# FubarStep_v10.net
KiCad netlist of a schematic drawn in EAGLE
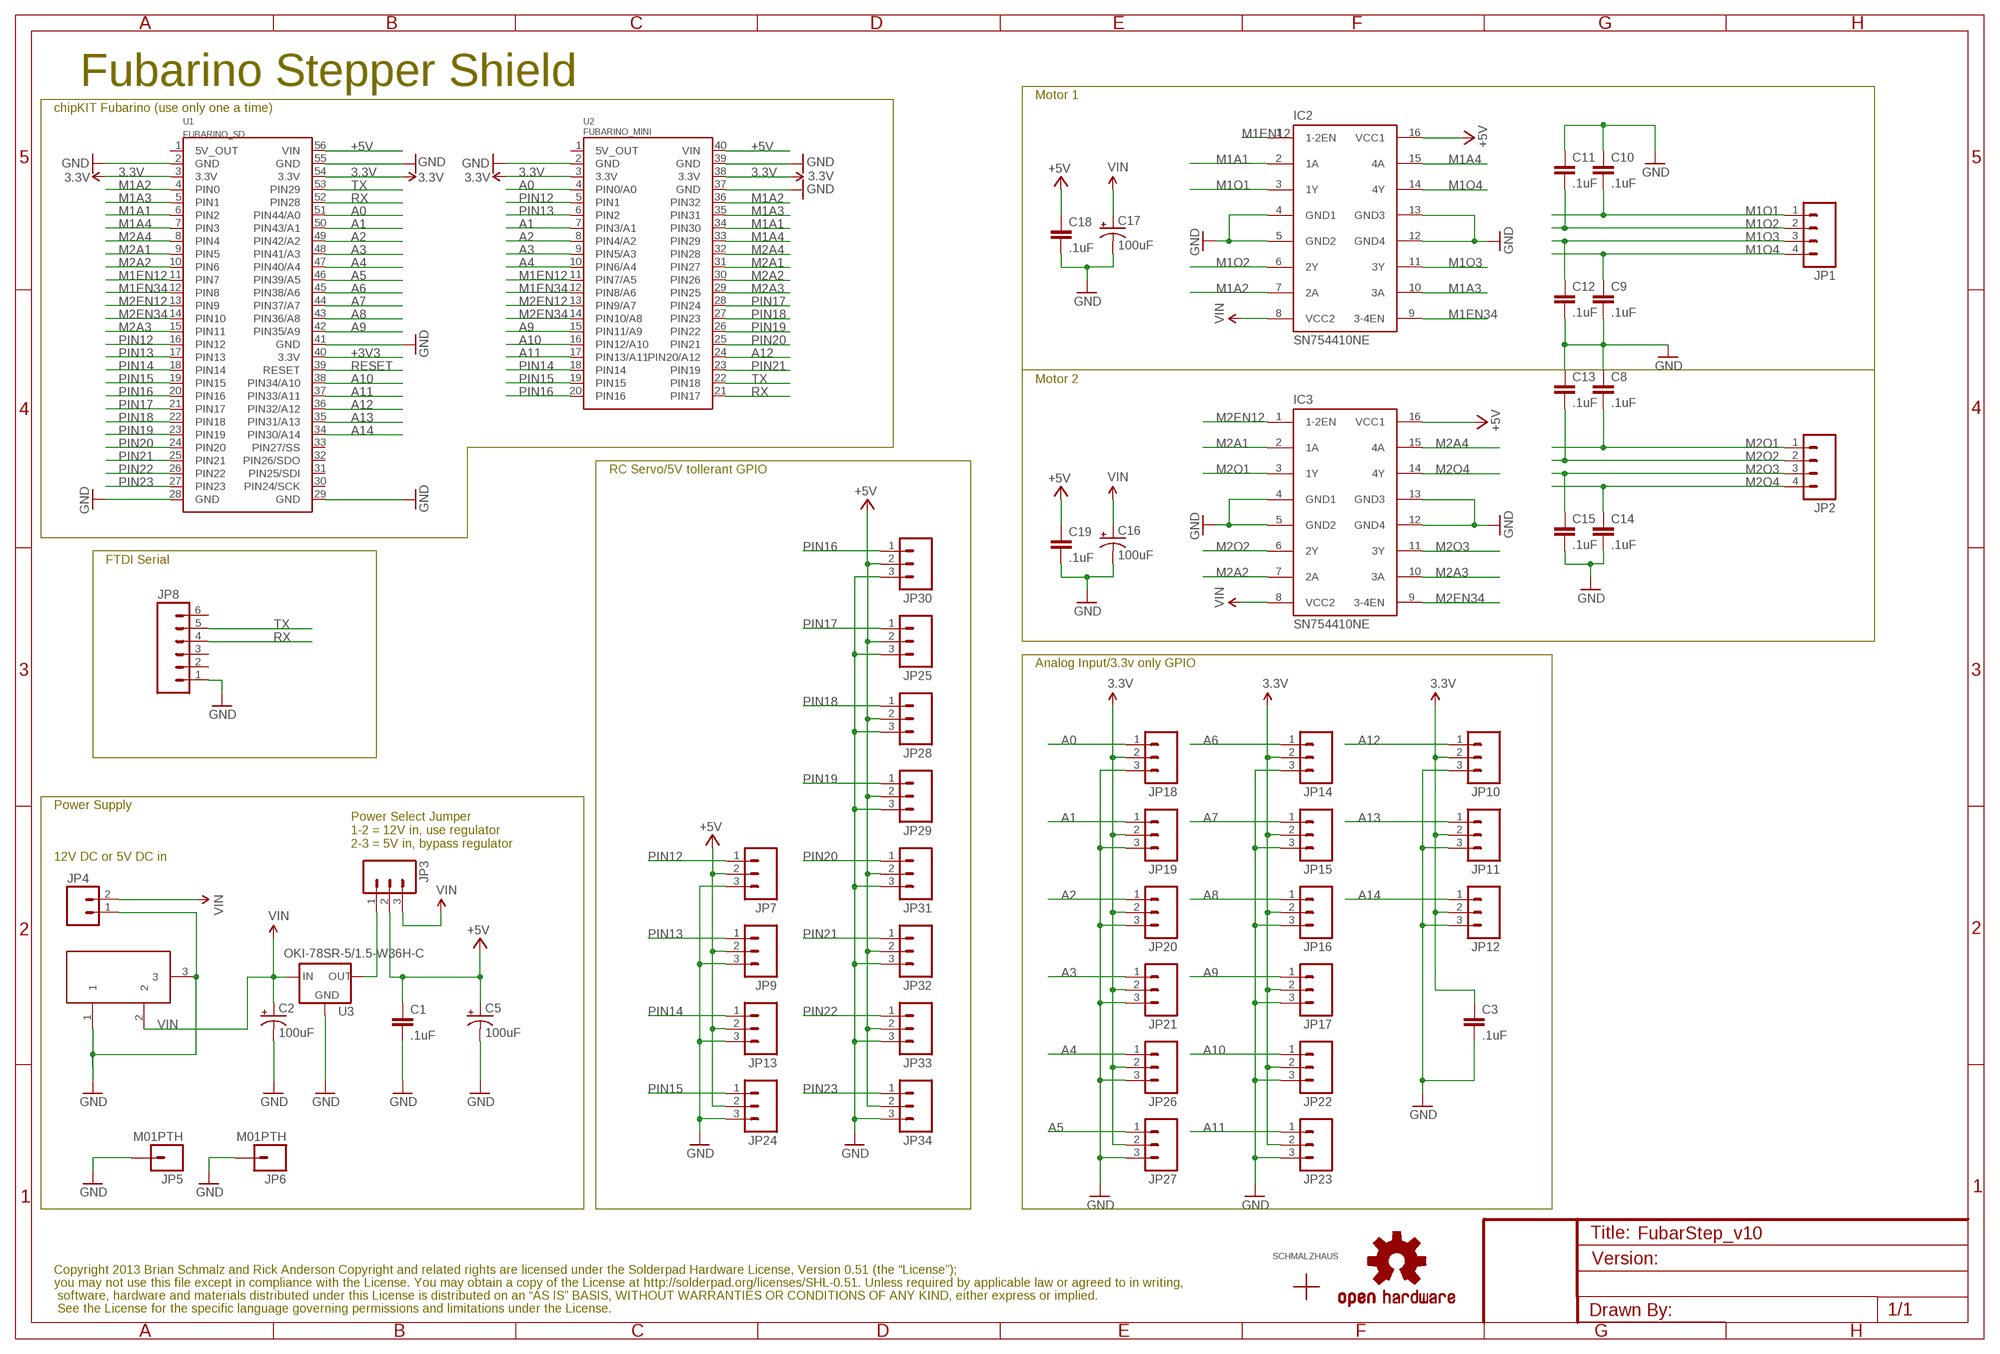
[diagram p0: schematic, sheet 1]

(export (version "E")
  (design (tool "Eeschema 10.0.6"))
  (components
    (comp (ref "C1")
      (value ".1uF")
      (footprint "eagle-import:CAP-PTH-SMALL")
      (libsource (lib "eagle-import") (part "CAPPTH"))
    )
    (comp (ref "C2")
      (value "100uF")
      (footprint "eagle-import:CPOL-RADIAL-100UF-25V")
      (libsource (lib "eagle-import") (part "CAP_POLPTH1"))
    )
    (comp (ref "C3")
      (value ".1uF")
      (footprint "eagle-import:CAP-PTH-SMALL")
      (libsource (lib "eagle-import") (part "CAPPTH"))
    )
    (comp (ref "C5")
      (value "100uF")
      (footprint "eagle-import:CPOL-RADIAL-100UF-25V")
      (libsource (lib "eagle-import") (part "CAP_POLPTH1"))
    )
    (comp (ref "C8")
      (value ".1uF")
      (footprint "eagle-import:CAP-PTH-SMALL")
      (libsource (lib "eagle-import") (part "CAPPTH"))
    )
    (comp (ref "C9")
      (value ".1uF")
      (footprint "eagle-import:CAP-PTH-SMALL")
      (libsource (lib "eagle-import") (part "CAPPTH"))
    )
    (comp (ref "C10")
      (value ".1uF")
      (footprint "eagle-import:CAP-PTH-SMALL")
      (libsource (lib "eagle-import") (part "CAPPTH"))
    )
    (comp (ref "C11")
      (value ".1uF")
      (footprint "eagle-import:CAP-PTH-SMALL")
      (libsource (lib "eagle-import") (part "CAPPTH"))
    )
    (comp (ref "C12")
      (value ".1uF")
      (footprint "eagle-import:CAP-PTH-SMALL")
      (libsource (lib "eagle-import") (part "CAPPTH"))
    )
    (comp (ref "C13")
      (value ".1uF")
      (footprint "eagle-import:CAP-PTH-SMALL")
      (libsource (lib "eagle-import") (part "CAPPTH"))
    )
    (comp (ref "C14")
      (value ".1uF")
      (footprint "eagle-import:CAP-PTH-SMALL")
      (libsource (lib "eagle-import") (part "CAPPTH"))
    )
    (comp (ref "C15")
      (value ".1uF")
      (footprint "eagle-import:CAP-PTH-SMALL")
      (libsource (lib "eagle-import") (part "CAPPTH"))
    )
    (comp (ref "C16")
      (value "100uF")
      (footprint "eagle-import:CPOL-RADIAL-100UF-25V")
      (libsource (lib "eagle-import") (part "CAP_POLPTH1"))
    )
    (comp (ref "C17")
      (value "100uF")
      (footprint "eagle-import:CPOL-RADIAL-100UF-25V")
      (libsource (lib "eagle-import") (part "CAP_POLPTH1"))
    )
    (comp (ref "C18")
      (value ".1uF")
      (footprint "eagle-import:CAP-PTH-SMALL")
      (libsource (lib "eagle-import") (part "CAPPTH"))
    )
    (comp (ref "C19")
      (value ".1uF")
      (footprint "eagle-import:CAP-PTH-SMALL")
      (libsource (lib "eagle-import") (part "CAPPTH"))
    )
    (comp (ref "IC2")
      (value "SN754410NE")
      (footprint "eagle-import:DIL16")
      (fields (field (name "MF") "Arrow Electronics") (field (name "MPN") "L293E"))
      (libsource (lib "eagle-import") (part "L293E"))
    )
    (comp (ref "IC3")
      (value "SN754410NE")
      (footprint "eagle-import:DIL16")
      (fields (field (name "MF") "Arrow Electronics") (field (name "MPN") "L293E"))
      (libsource (lib "eagle-import") (part "L293E"))
    )
    (comp (ref "JP1")
      (value "M04SCREW_LOCK")
      (footprint "eagle-import:SCREWTERMINAL-3.5MM-4_LOCK")
      (libsource (lib "eagle-import") (part "M04SCREW_LOCK"))
    )
    (comp (ref "JP2")
      (value "M04SCREW_LOCK")
      (footprint "eagle-import:SCREWTERMINAL-3.5MM-4_LOCK")
      (libsource (lib "eagle-import") (part "M04SCREW_LOCK"))
    )
    (comp (ref "JP3")
      (value "M03PTH")
      (footprint "eagle-import:1X03")
      (libsource (lib "eagle-import") (part "M03PTH"))
    )
    (comp (ref "JP4")
      (value "M023.5MM")
      (footprint "eagle-import:SCREWTERMINAL-3.5MM-2")
      (libsource (lib "eagle-import") (part "M023.5MM"))
    )
    (comp (ref "JP5")
      (value "M01PTH")
      (footprint "eagle-import:1X01")
      (libsource (lib "eagle-import") (part "M01PTH"))
    )
    (comp (ref "JP6")
      (value "M01PTH")
      (footprint "eagle-import:1X01")
      (libsource (lib "eagle-import") (part "M01PTH"))
    )
    (comp (ref "JP7")
      (value "M03PTH")
      (footprint "eagle-import:1X03")
      (libsource (lib "eagle-import") (part "M03PTH"))
    )
    (comp (ref "JP8")
      (value "M06LOCK")
      (footprint "eagle-import:1X06_LOCK")
      (libsource (lib "eagle-import") (part "M06LOCK"))
    )
    (comp (ref "JP9")
      (value "M03PTH")
      (footprint "eagle-import:1X03")
      (libsource (lib "eagle-import") (part "M03PTH"))
    )
    (comp (ref "JP10")
      (value "M03PTH")
      (footprint "eagle-import:1X03")
      (libsource (lib "eagle-import") (part "M03PTH"))
    )
    (comp (ref "JP11")
      (value "M03PTH")
      (footprint "eagle-import:1X03")
      (libsource (lib "eagle-import") (part "M03PTH"))
    )
    (comp (ref "JP12")
      (value "M03PTH")
      (footprint "eagle-import:1X03")
      (libsource (lib "eagle-import") (part "M03PTH"))
    )
    (comp (ref "JP13")
      (value "M03PTH")
      (footprint "eagle-import:1X03")
      (libsource (lib "eagle-import") (part "M03PTH"))
    )
    (comp (ref "JP14")
      (value "M03PTH")
      (footprint "eagle-import:1X03")
      (libsource (lib "eagle-import") (part "M03PTH"))
    )
    (comp (ref "JP15")
      (value "M03PTH")
      (footprint "eagle-import:1X03")
      (libsource (lib "eagle-import") (part "M03PTH"))
    )
    (comp (ref "JP16")
      (value "M03PTH")
      (footprint "eagle-import:1X03")
      (libsource (lib "eagle-import") (part "M03PTH"))
    )
    (comp (ref "JP17")
      (value "M03PTH")
      (footprint "eagle-import:1X03")
      (libsource (lib "eagle-import") (part "M03PTH"))
    )
    (comp (ref "JP18")
      (value "M03PTH")
      (footprint "eagle-import:1X03")
      (libsource (lib "eagle-import") (part "M03PTH"))
    )
    (comp (ref "JP19")
      (value "M03PTH")
      (footprint "eagle-import:1X03")
      (libsource (lib "eagle-import") (part "M03PTH"))
    )
    (comp (ref "JP20")
      (value "M03PTH")
      (footprint "eagle-import:1X03")
      (libsource (lib "eagle-import") (part "M03PTH"))
    )
    (comp (ref "JP21")
      (value "M03PTH")
      (footprint "eagle-import:1X03")
      (libsource (lib "eagle-import") (part "M03PTH"))
    )
    (comp (ref "JP22")
      (value "M03PTH")
      (footprint "eagle-import:1X03")
      (libsource (lib "eagle-import") (part "M03PTH"))
    )
    (comp (ref "JP23")
      (value "M03PTH")
      (footprint "eagle-import:1X03")
      (libsource (lib "eagle-import") (part "M03PTH"))
    )
    (comp (ref "JP24")
      (value "M03PTH")
      (footprint "eagle-import:1X03")
      (libsource (lib "eagle-import") (part "M03PTH"))
    )
    (comp (ref "JP25")
      (value "M03PTH")
      (footprint "eagle-import:1X03")
      (libsource (lib "eagle-import") (part "M03PTH"))
    )
    (comp (ref "JP26")
      (value "M03PTH")
      (footprint "eagle-import:1X03")
      (libsource (lib "eagle-import") (part "M03PTH"))
    )
    (comp (ref "JP27")
      (value "M03PTH")
      (footprint "eagle-import:1X03")
      (libsource (lib "eagle-import") (part "M03PTH"))
    )
    (comp (ref "JP28")
      (value "M03PTH")
      (footprint "eagle-import:1X03")
      (libsource (lib "eagle-import") (part "M03PTH"))
    )
    (comp (ref "JP29")
      (value "M03PTH")
      (footprint "eagle-import:1X03")
      (libsource (lib "eagle-import") (part "M03PTH"))
    )
    (comp (ref "JP30")
      (value "M03PTH")
      (footprint "eagle-import:1X03")
      (libsource (lib "eagle-import") (part "M03PTH"))
    )
    (comp (ref "JP31")
      (value "M03PTH")
      (footprint "eagle-import:1X03")
      (libsource (lib "eagle-import") (part "M03PTH"))
    )
    (comp (ref "JP32")
      (value "M03PTH")
      (footprint "eagle-import:1X03")
      (libsource (lib "eagle-import") (part "M03PTH"))
    )
    (comp (ref "JP33")
      (value "M03PTH")
      (footprint "eagle-import:1X03")
      (libsource (lib "eagle-import") (part "M03PTH"))
    )
    (comp (ref "JP34")
      (value "M03PTH")
      (footprint "eagle-import:1X03")
      (libsource (lib "eagle-import") (part "M03PTH"))
    )
    (comp (ref "LOGO1")
      (value "OSHW-LOGOM")
      (footprint "eagle-import:OSHW-LOGO-M")
      (libsource (lib "eagle-import") (part "OSHW-LOGOM"))
    )
    (comp (ref "U$1")
      (value "SCHMALZHAUSSCHMALZHAUS_SMALL")
      (footprint "eagle-import:SCHMALZHAUS_SMALL")
      (libsource (lib "eagle-import") (part "SCHMALZHAUSSCHMALZHAUS_SMALL"))
    )
    (comp (ref "U1")
      (value "FUBARINO_SD")
      (footprint "eagle-import:FUBARINO_SD")
      (libsource (lib "eagle-import") (part "FUBARINO_SD"))
    )
    (comp (ref "U2")
      (value "FUBARINO_MINI")
      (footprint "eagle-import:FUBARINO_MINI")
      (libsource (lib "eagle-import") (part "FUBARINO_MINI"))
    )
    (comp (ref "U3")
      (value "OKI-78SR-5/1.5-W36H-C")
      (footprint "eagle-import:TO220-IGO")
      (libsource (lib "eagle-import") (part "V_REG_78XXSINK"))
    )
    (comp (ref "X1")
      (value "DC21MMX")
      (footprint "eagle-import:DC-21MM")
      (libsource (lib "eagle-import") (part "DC21MMX"))
    )
  )
  (nets
    (net (code "1") (name "+5V") (class "Default")
      (node (ref "C1") (pin "1") (pinfunction "1_1") (pintype "passive"))
      (node (ref "C18") (pin "1") (pinfunction "1_1") (pintype "passive"))
      (node (ref "C19") (pin "1") (pinfunction "1_1") (pintype "passive"))
      (node (ref "C5") (pin "1") (pinfunction "+_1") (pintype "passive"))
      (node (ref "IC2") (pin "16") (pinfunction "VCC1_16") (pintype "power_in"))
      (node (ref "IC3") (pin "16") (pinfunction "VCC1_16") (pintype "power_in"))
      (node (ref "JP13") (pin "2") (pinfunction "2_2") (pintype "passive"))
      (node (ref "JP24") (pin "2") (pinfunction "2_2") (pintype "passive"))
      (node (ref "JP25") (pin "2") (pinfunction "2_2") (pintype "passive"))
      (node (ref "JP28") (pin "2") (pinfunction "2_2") (pintype "passive"))
      (node (ref "JP29") (pin "2") (pinfunction "2_2") (pintype "passive"))
      (node (ref "JP3") (pin "2") (pinfunction "2_2") (pintype "passive"))
      (node (ref "JP30") (pin "2") (pinfunction "2_2") (pintype "passive"))
      (node (ref "JP31") (pin "2") (pinfunction "2_2") (pintype "passive"))
      (node (ref "JP32") (pin "2") (pinfunction "2_2") (pintype "passive"))
      (node (ref "JP33") (pin "2") (pinfunction "2_2") (pintype "passive"))
      (node (ref "JP34") (pin "2") (pinfunction "2_2") (pintype "passive"))
      (node (ref "JP7") (pin "2") (pinfunction "2_2") (pintype "passive"))
      (node (ref "JP9") (pin "2") (pinfunction "2_2") (pintype "passive"))
      (node (ref "U1") (pin "56") (pinfunction "VIN_56") (pintype "bidirectional"))
      (node (ref "U2") (pin "40") (pinfunction "VIN_40") (pintype "bidirectional"))
    )
    (net (code "2") (name "/+3V3") (class "Default")
      (node (ref "U1") (pin "40") (pinfunction "3.3V_40") (pintype "bidirectional"))
    )
    (net (code "3") (name "/A0") (class "Default")
      (node (ref "JP18") (pin "1") (pinfunction "1_1") (pintype "passive"))
      (node (ref "U1") (pin "51") (pinfunction "PIN44/A0_51") (pintype "bidirectional"))
      (node (ref "U2") (pin "4") (pinfunction "PIN0/A0_4") (pintype "bidirectional"))
    )
    (net (code "4") (name "/A1") (class "Default")
      (node (ref "JP19") (pin "1") (pinfunction "1_1") (pintype "passive"))
      (node (ref "U1") (pin "50") (pinfunction "PIN43/A1_50") (pintype "bidirectional"))
      (node (ref "U2") (pin "7") (pinfunction "PIN3/A1_7") (pintype "bidirectional"))
    )
    (net (code "5") (name "/A2") (class "Default")
      (node (ref "JP20") (pin "1") (pinfunction "1_1") (pintype "passive"))
      (node (ref "U1") (pin "49") (pinfunction "PIN42/A2_49") (pintype "bidirectional"))
      (node (ref "U2") (pin "8") (pinfunction "PIN4/A2_8") (pintype "bidirectional"))
    )
    (net (code "6") (name "/A3") (class "Default")
      (node (ref "JP21") (pin "1") (pinfunction "1_1") (pintype "passive"))
      (node (ref "U1") (pin "48") (pinfunction "PIN41/A3_48") (pintype "bidirectional"))
      (node (ref "U2") (pin "9") (pinfunction "PIN5/A3_9") (pintype "bidirectional"))
    )
    (net (code "7") (name "/A4") (class "Default")
      (node (ref "JP26") (pin "1") (pinfunction "1_1") (pintype "passive"))
      (node (ref "U1") (pin "47") (pinfunction "PIN40/A4_47") (pintype "bidirectional"))
      (node (ref "U2") (pin "10") (pinfunction "PIN6/A4_10") (pintype "bidirectional"))
    )
    (net (code "8") (name "/A5") (class "Default")
      (node (ref "JP27") (pin "1") (pinfunction "1_1") (pintype "passive"))
      (node (ref "U1") (pin "46") (pinfunction "PIN39/A5_46") (pintype "bidirectional"))
    )
    (net (code "9") (name "/A6") (class "Default")
      (node (ref "JP14") (pin "1") (pinfunction "1_1") (pintype "passive"))
      (node (ref "U1") (pin "45") (pinfunction "PIN38/A6_45") (pintype "bidirectional"))
    )
    (net (code "10") (name "/A7") (class "Default")
      (node (ref "JP15") (pin "1") (pinfunction "1_1") (pintype "passive"))
      (node (ref "U1") (pin "44") (pinfunction "PIN37/A7_44") (pintype "bidirectional"))
    )
    (net (code "11") (name "/A8") (class "Default")
      (node (ref "JP16") (pin "1") (pinfunction "1_1") (pintype "passive"))
      (node (ref "U1") (pin "43") (pinfunction "PIN36/A8_43") (pintype "bidirectional"))
    )
    (net (code "12") (name "/A9") (class "Default")
      (node (ref "JP17") (pin "1") (pinfunction "1_1") (pintype "passive"))
      (node (ref "U1") (pin "42") (pinfunction "PIN35/A9_42") (pintype "bidirectional"))
      (node (ref "U2") (pin "15") (pinfunction "PIN11/A9_15") (pintype "bidirectional"))
    )
    (net (code "13") (name "/A10") (class "Default")
      (node (ref "JP22") (pin "1") (pinfunction "1_1") (pintype "passive"))
      (node (ref "U1") (pin "38") (pinfunction "PIN34/A10_38") (pintype "bidirectional"))
      (node (ref "U2") (pin "16") (pinfunction "PIN12/A10_16") (pintype "bidirectional"))
    )
    (net (code "14") (name "/A11") (class "Default")
      (node (ref "JP23") (pin "1") (pinfunction "1_1") (pintype "passive"))
      (node (ref "U1") (pin "37") (pinfunction "PIN33/A11_37") (pintype "bidirectional"))
      (node (ref "U2") (pin "17") (pinfunction "PIN13/A11_17") (pintype "bidirectional"))
    )
    (net (code "15") (name "/A12") (class "Default")
      (node (ref "JP10") (pin "1") (pinfunction "1_1") (pintype "passive"))
      (node (ref "U1") (pin "36") (pinfunction "PIN32/A12_36") (pintype "bidirectional"))
      (node (ref "U2") (pin "24") (pinfunction "PIN20/A12_24") (pintype "bidirectional"))
    )
    (net (code "16") (name "/A13") (class "Default")
      (node (ref "JP11") (pin "1") (pinfunction "1_1") (pintype "passive"))
      (node (ref "U1") (pin "35") (pinfunction "PIN31/A13_35") (pintype "bidirectional"))
    )
    (net (code "17") (name "/A14") (class "Default")
      (node (ref "JP12") (pin "1") (pinfunction "1_1") (pintype "passive"))
      (node (ref "U1") (pin "34") (pinfunction "PIN30/A14_34") (pintype "bidirectional"))
    )
    (net (code "18") (name "/M1A1") (class "Default")
      (node (ref "IC2") (pin "2") (pinfunction "1A_2") (pintype "input"))
      (node (ref "U1") (pin "6") (pinfunction "PIN2_6") (pintype "bidirectional"))
      (node (ref "U2") (pin "34") (pinfunction "PIN30_34") (pintype "bidirectional"))
    )
    (net (code "19") (name "/M1A2") (class "Default")
      (node (ref "IC2") (pin "7") (pinfunction "2A_7") (pintype "input"))
      (node (ref "U1") (pin "4") (pinfunction "PIN0_4") (pintype "bidirectional"))
      (node (ref "U2") (pin "36") (pinfunction "PIN32_36") (pintype "bidirectional"))
    )
    (net (code "20") (name "/M1A3") (class "Default")
      (node (ref "IC2") (pin "10") (pinfunction "3A_10") (pintype "input"))
      (node (ref "U1") (pin "5") (pinfunction "PIN1_5") (pintype "bidirectional"))
      (node (ref "U2") (pin "35") (pinfunction "PIN31_35") (pintype "bidirectional"))
    )
    (net (code "21") (name "/M1A4") (class "Default")
      (node (ref "IC2") (pin "15") (pinfunction "4A_15") (pintype "input"))
      (node (ref "U1") (pin "7") (pinfunction "PIN3_7") (pintype "bidirectional"))
      (node (ref "U2") (pin "33") (pinfunction "PIN29_33") (pintype "bidirectional"))
    )
    (net (code "22") (name "/M1EN12") (class "Default")
      (node (ref "IC2") (pin "1") (pinfunction "1-2EN_1") (pintype "input"))
      (node (ref "U1") (pin "11") (pinfunction "PIN7_11") (pintype "bidirectional"))
      (node (ref "U2") (pin "11") (pinfunction "PIN7/A5_11") (pintype "bidirectional"))
    )
    (net (code "23") (name "/M1EN34") (class "Default")
      (node (ref "IC2") (pin "9") (pinfunction "3-4EN_9") (pintype "input"))
      (node (ref "U1") (pin "12") (pinfunction "PIN8_12") (pintype "bidirectional"))
      (node (ref "U2") (pin "12") (pinfunction "PIN8/A6_12") (pintype "bidirectional"))
    )
    (net (code "24") (name "/M1O1") (class "Default")
      (node (ref "C10") (pin "2") (pinfunction "2_2") (pintype "passive"))
      (node (ref "IC2") (pin "3") (pinfunction "1Y_3") (pintype "output"))
      (node (ref "JP1") (pin "1") (pinfunction "1_1") (pintype "passive"))
    )
    (net (code "25") (name "/M1O2") (class "Default")
      (node (ref "C11") (pin "2") (pinfunction "2_2") (pintype "passive"))
      (node (ref "IC2") (pin "6") (pinfunction "2Y_6") (pintype "output"))
      (node (ref "JP1") (pin "2") (pinfunction "2_2") (pintype "passive"))
    )
    (net (code "26") (name "/M1O3") (class "Default")
      (node (ref "C12") (pin "1") (pinfunction "1_1") (pintype "passive"))
      (node (ref "IC2") (pin "11") (pinfunction "3Y_11") (pintype "output"))
      (node (ref "JP1") (pin "3") (pinfunction "3_3") (pintype "passive"))
    )
    (net (code "27") (name "/M1O4") (class "Default")
      (node (ref "C9") (pin "1") (pinfunction "1_1") (pintype "passive"))
      (node (ref "IC2") (pin "14") (pinfunction "4Y_14") (pintype "output"))
      (node (ref "JP1") (pin "4") (pinfunction "4_4") (pintype "passive"))
    )
    (net (code "28") (name "/M2A1") (class "Default")
      (node (ref "IC3") (pin "2") (pinfunction "1A_2") (pintype "input"))
      (node (ref "U1") (pin "9") (pinfunction "PIN5_9") (pintype "bidirectional"))
      (node (ref "U2") (pin "31") (pinfunction "PIN27_31") (pintype "bidirectional"))
    )
    (net (code "29") (name "/M2A2") (class "Default")
      (node (ref "IC3") (pin "7") (pinfunction "2A_7") (pintype "input"))
      (node (ref "U1") (pin "10") (pinfunction "PIN6_10") (pintype "bidirectional"))
      (node (ref "U2") (pin "30") (pinfunction "PIN26_30") (pintype "bidirectional"))
    )
    (net (code "30") (name "/M2A3") (class "Default")
      (node (ref "IC3") (pin "10") (pinfunction "3A_10") (pintype "input"))
      (node (ref "U1") (pin "15") (pinfunction "PIN11_15") (pintype "bidirectional"))
      (node (ref "U2") (pin "29") (pinfunction "PIN25_29") (pintype "bidirectional"))
    )
    (net (code "31") (name "/M2A4") (class "Default")
      (node (ref "IC3") (pin "15") (pinfunction "4A_15") (pintype "input"))
      (node (ref "U1") (pin "8") (pinfunction "PIN4_8") (pintype "bidirectional"))
      (node (ref "U2") (pin "32") (pinfunction "PIN28_32") (pintype "bidirectional"))
    )
    (net (code "32") (name "/M2EN12") (class "Default")
      (node (ref "IC3") (pin "1") (pinfunction "1-2EN_1") (pintype "input"))
      (node (ref "U1") (pin "13") (pinfunction "PIN9_13") (pintype "bidirectional"))
      (node (ref "U2") (pin "13") (pinfunction "PIN9/A7_13") (pintype "bidirectional"))
    )
    (net (code "33") (name "/M2EN34") (class "Default")
      (node (ref "IC3") (pin "9") (pinfunction "3-4EN_9") (pintype "input"))
      (node (ref "U1") (pin "14") (pinfunction "PIN10_14") (pintype "bidirectional"))
      (node (ref "U2") (pin "14") (pinfunction "PIN10/A8_14") (pintype "bidirectional"))
    )
    (net (code "34") (name "/M2O1") (class "Default")
      (node (ref "C8") (pin "2") (pinfunction "2_2") (pintype "passive"))
      (node (ref "IC3") (pin "3") (pinfunction "1Y_3") (pintype "output"))
      (node (ref "JP2") (pin "1") (pinfunction "1_1") (pintype "passive"))
    )
    (net (code "35") (name "/M2O2") (class "Default")
      (node (ref "C13") (pin "2") (pinfunction "2_2") (pintype "passive"))
      (node (ref "IC3") (pin "6") (pinfunction "2Y_6") (pintype "output"))
      (node (ref "JP2") (pin "2") (pinfunction "2_2") (pintype "passive"))
    )
    (net (code "36") (name "/M2O3") (class "Default")
      (node (ref "C15") (pin "1") (pinfunction "1_1") (pintype "passive"))
      (node (ref "IC3") (pin "11") (pinfunction "3Y_11") (pintype "output"))
      (node (ref "JP2") (pin "3") (pinfunction "3_3") (pintype "passive"))
    )
    (net (code "37") (name "/M2O4") (class "Default")
      (node (ref "C14") (pin "1") (pinfunction "1_1") (pintype "passive"))
      (node (ref "IC3") (pin "14") (pinfunction "4Y_14") (pintype "output"))
      (node (ref "JP2") (pin "4") (pinfunction "4_4") (pintype "passive"))
    )
    (net (code "38") (name "/PIN12") (class "Default")
      (node (ref "JP7") (pin "1") (pinfunction "1_1") (pintype "passive"))
      (node (ref "U1") (pin "16") (pinfunction "PIN12_16") (pintype "bidirectional"))
      (node (ref "U2") (pin "5") (pinfunction "PIN1_5") (pintype "bidirectional"))
    )
    (net (code "39") (name "/PIN13") (class "Default")
      (node (ref "JP9") (pin "1") (pinfunction "1_1") (pintype "passive"))
      (node (ref "U1") (pin "17") (pinfunction "PIN13_17") (pintype "bidirectional"))
      (node (ref "U2") (pin "6") (pinfunction "PIN2_6") (pintype "bidirectional"))
    )
    (net (code "40") (name "/PIN14") (class "Default")
      (node (ref "JP13") (pin "1") (pinfunction "1_1") (pintype "passive"))
      (node (ref "U1") (pin "18") (pinfunction "PIN14_18") (pintype "bidirectional"))
      (node (ref "U2") (pin "18") (pinfunction "PIN14_18") (pintype "bidirectional"))
    )
    (net (code "41") (name "/PIN15") (class "Default")
      (node (ref "JP24") (pin "1") (pinfunction "1_1") (pintype "passive"))
      (node (ref "U1") (pin "19") (pinfunction "PIN15_19") (pintype "bidirectional"))
      (node (ref "U2") (pin "19") (pinfunction "PIN15_19") (pintype "bidirectional"))
    )
    (net (code "42") (name "/PIN16") (class "Default")
      (node (ref "JP30") (pin "1") (pinfunction "1_1") (pintype "passive"))
      (node (ref "U1") (pin "20") (pinfunction "PIN16_20") (pintype "bidirectional"))
      (node (ref "U2") (pin "20") (pinfunction "PIN16_20") (pintype "bidirectional"))
    )
    (net (code "43") (name "/PIN17") (class "Default")
      (node (ref "JP25") (pin "1") (pinfunction "1_1") (pintype "passive"))
      (node (ref "U1") (pin "21") (pinfunction "PIN17_21") (pintype "bidirectional"))
      (node (ref "U2") (pin "28") (pinfunction "PIN24_28") (pintype "bidirectional"))
    )
    (net (code "44") (name "/PIN18") (class "Default")
      (node (ref "JP28") (pin "1") (pinfunction "1_1") (pintype "passive"))
      (node (ref "U1") (pin "22") (pinfunction "PIN18_22") (pintype "bidirectional"))
      (node (ref "U2") (pin "27") (pinfunction "PIN23_27") (pintype "bidirectional"))
    )
    (net (code "45") (name "/PIN19") (class "Default")
      (node (ref "JP29") (pin "1") (pinfunction "1_1") (pintype "passive"))
      (node (ref "U1") (pin "23") (pinfunction "PIN19_23") (pintype "bidirectional"))
      (node (ref "U2") (pin "26") (pinfunction "PIN22_26") (pintype "bidirectional"))
    )
    (net (code "46") (name "/PIN20") (class "Default")
      (node (ref "JP31") (pin "1") (pinfunction "1_1") (pintype "passive"))
      (node (ref "U1") (pin "24") (pinfunction "PIN20_24") (pintype "bidirectional"))
      (node (ref "U2") (pin "25") (pinfunction "PIN21_25") (pintype "bidirectional"))
    )
    (net (code "47") (name "/PIN21") (class "Default")
      (node (ref "JP32") (pin "1") (pinfunction "1_1") (pintype "passive"))
      (node (ref "U1") (pin "25") (pinfunction "PIN21_25") (pintype "bidirectional"))
      (node (ref "U2") (pin "23") (pinfunction "PIN19_23") (pintype "bidirectional"))
    )
    (net (code "48") (name "/PIN22") (class "Default")
      (node (ref "JP33") (pin "1") (pinfunction "1_1") (pintype "passive"))
      (node (ref "U1") (pin "26") (pinfunction "PIN22_26") (pintype "bidirectional"))
    )
    (net (code "49") (name "/PIN23") (class "Default")
      (node (ref "JP34") (pin "1") (pinfunction "1_1") (pintype "passive"))
      (node (ref "U1") (pin "27") (pinfunction "PIN23_27") (pintype "bidirectional"))
    )
    (net (code "50") (name "/RESET") (class "Default")
      (node (ref "U1") (pin "39") (pinfunction "RESET_39") (pintype "bidirectional"))
    )
    (net (code "51") (name "/RX") (class "Default")
      (node (ref "JP8") (pin "4") (pinfunction "4_4") (pintype "passive"))
      (node (ref "U1") (pin "52") (pinfunction "PIN28_52") (pintype "bidirectional"))
      (node (ref "U2") (pin "21") (pinfunction "PIN17_21") (pintype "bidirectional"))
    )
    (net (code "52") (name "/TX") (class "Default")
      (node (ref "JP8") (pin "5") (pinfunction "5_5") (pintype "passive"))
      (node (ref "U1") (pin "53") (pinfunction "PIN29_53") (pintype "bidirectional"))
      (node (ref "U2") (pin "22") (pinfunction "PIN18_22") (pintype "bidirectional"))
    )
    (net (code "53") (name "3.3V") (class "Default")
      (node (ref "C3") (pin "1") (pinfunction "1_1") (pintype "passive"))
      (node (ref "JP10") (pin "2") (pinfunction "2_2") (pintype "passive"))
      (node (ref "JP11") (pin "2") (pinfunction "2_2") (pintype "passive"))
      (node (ref "JP12") (pin "2") (pinfunction "2_2") (pintype "passive"))
      (node (ref "JP14") (pin "2") (pinfunction "2_2") (pintype "passive"))
      (node (ref "JP15") (pin "2") (pinfunction "2_2") (pintype "passive"))
      (node (ref "JP16") (pin "2") (pinfunction "2_2") (pintype "passive"))
      (node (ref "JP17") (pin "2") (pinfunction "2_2") (pintype "passive"))
      (node (ref "JP18") (pin "2") (pinfunction "2_2") (pintype "passive"))
      (node (ref "JP19") (pin "2") (pinfunction "2_2") (pintype "passive"))
      (node (ref "JP20") (pin "2") (pinfunction "2_2") (pintype "passive"))
      (node (ref "JP21") (pin "2") (pinfunction "2_2") (pintype "passive"))
      (node (ref "JP22") (pin "2") (pinfunction "2_2") (pintype "passive"))
      (node (ref "JP23") (pin "2") (pinfunction "2_2") (pintype "passive"))
      (node (ref "JP26") (pin "2") (pinfunction "2_2") (pintype "passive"))
      (node (ref "JP27") (pin "2") (pinfunction "2_2") (pintype "passive"))
      (node (ref "U1") (pin "3") (pinfunction "3.3V_3") (pintype "bidirectional"))
      (node (ref "U1") (pin "54") (pinfunction "3.3V_54") (pintype "bidirectional"))
      (node (ref "U2") (pin "3") (pinfunction "3.3V_3") (pintype "bidirectional"))
      (node (ref "U2") (pin "38") (pinfunction "3.3V_38") (pintype "bidirectional"))
    )
    (net (code "54") (name "GND") (class "Default")
      (node (ref "C1") (pin "2") (pinfunction "2_2") (pintype "passive"))
      (node (ref "C10") (pin "1") (pinfunction "1_1") (pintype "passive"))
      (node (ref "C11") (pin "1") (pinfunction "1_1") (pintype "passive"))
      (node (ref "C12") (pin "2") (pinfunction "2_2") (pintype "passive"))
      (node (ref "C13") (pin "1") (pinfunction "1_1") (pintype "passive"))
      (node (ref "C14") (pin "2") (pinfunction "2_2") (pintype "passive"))
      (node (ref "C15") (pin "2") (pinfunction "2_2") (pintype "passive"))
      (node (ref "C16") (pin "2") (pinfunction "-_2") (pintype "passive"))
      (node (ref "C17") (pin "2") (pinfunction "-_2") (pintype "passive"))
      (node (ref "C18") (pin "2") (pinfunction "2_2") (pintype "passive"))
      (node (ref "C19") (pin "2") (pinfunction "2_2") (pintype "passive"))
      (node (ref "C2") (pin "2") (pinfunction "-_2") (pintype "passive"))
      (node (ref "C3") (pin "2") (pinfunction "2_2") (pintype "passive"))
      (node (ref "C5") (pin "2") (pinfunction "-_2") (pintype "passive"))
      (node (ref "C8") (pin "1") (pinfunction "1_1") (pintype "passive"))
      (node (ref "C9") (pin "2") (pinfunction "2_2") (pintype "passive"))
      (node (ref "IC2") (pin "12") (pinfunction "GND4_12") (pintype "power_in"))
      (node (ref "IC2") (pin "13") (pinfunction "GND3_13") (pintype "power_in"))
      (node (ref "IC2") (pin "4") (pinfunction "GND1_4") (pintype "power_in"))
      (node (ref "IC2") (pin "5") (pinfunction "GND2_5") (pintype "power_in"))
      (node (ref "IC3") (pin "12") (pinfunction "GND4_12") (pintype "power_in"))
      (node (ref "IC3") (pin "13") (pinfunction "GND3_13") (pintype "power_in"))
      (node (ref "IC3") (pin "4") (pinfunction "GND1_4") (pintype "power_in"))
      (node (ref "IC3") (pin "5") (pinfunction "GND2_5") (pintype "power_in"))
      (node (ref "JP10") (pin "3") (pinfunction "3_3") (pintype "passive"))
      (node (ref "JP11") (pin "3") (pinfunction "3_3") (pintype "passive"))
      (node (ref "JP12") (pin "3") (pinfunction "3_3") (pintype "passive"))
      (node (ref "JP13") (pin "3") (pinfunction "3_3") (pintype "passive"))
      (node (ref "JP14") (pin "3") (pinfunction "3_3") (pintype "passive"))
      (node (ref "JP15") (pin "3") (pinfunction "3_3") (pintype "passive"))
      (node (ref "JP16") (pin "3") (pinfunction "3_3") (pintype "passive"))
      (node (ref "JP17") (pin "3") (pinfunction "3_3") (pintype "passive"))
      (node (ref "JP18") (pin "3") (pinfunction "3_3") (pintype "passive"))
      (node (ref "JP19") (pin "3") (pinfunction "3_3") (pintype "passive"))
      (node (ref "JP20") (pin "3") (pinfunction "3_3") (pintype "passive"))
      (node (ref "JP21") (pin "3") (pinfunction "3_3") (pintype "passive"))
      (node (ref "JP22") (pin "3") (pinfunction "3_3") (pintype "passive"))
      (node (ref "JP23") (pin "3") (pinfunction "3_3") (pintype "passive"))
      (node (ref "JP24") (pin "3") (pinfunction "3_3") (pintype "passive"))
      (node (ref "JP25") (pin "3") (pinfunction "3_3") (pintype "passive"))
      (node (ref "JP26") (pin "3") (pinfunction "3_3") (pintype "passive"))
      (node (ref "JP27") (pin "3") (pinfunction "3_3") (pintype "passive"))
      (node (ref "JP28") (pin "3") (pinfunction "3_3") (pintype "passive"))
      (node (ref "JP29") (pin "3") (pinfunction "3_3") (pintype "passive"))
      (node (ref "JP30") (pin "3") (pinfunction "3_3") (pintype "passive"))
      (node (ref "JP31") (pin "3") (pinfunction "3_3") (pintype "passive"))
      (node (ref "JP32") (pin "3") (pinfunction "3_3") (pintype "passive"))
      (node (ref "JP33") (pin "3") (pinfunction "3_3") (pintype "passive"))
      (node (ref "JP34") (pin "3") (pinfunction "3_3") (pintype "passive"))
      (node (ref "JP4") (pin "1") (pinfunction "1_1") (pintype "passive"))
      (node (ref "JP5") (pin "1") (pinfunction "1_1") (pintype "passive"))
      (node (ref "JP6") (pin "1") (pinfunction "1_1") (pintype "passive"))
      (node (ref "JP7") (pin "3") (pinfunction "3_3") (pintype "passive"))
      (node (ref "JP8") (pin "1") (pinfunction "1_1") (pintype "passive"))
      (node (ref "JP9") (pin "3") (pinfunction "3_3") (pintype "passive"))
      (node (ref "U1") (pin "2") (pinfunction "GND_2") (pintype "bidirectional"))
      (node (ref "U1") (pin "28") (pinfunction "GND_28") (pintype "bidirectional"))
      (node (ref "U1") (pin "29") (pinfunction "GND_29") (pintype "bidirectional"))
      (node (ref "U1") (pin "41") (pinfunction "GND_41") (pintype "bidirectional"))
      (node (ref "U1") (pin "55") (pinfunction "GND_55") (pintype "bidirectional"))
      (node (ref "U2") (pin "2") (pinfunction "GND_2") (pintype "bidirectional"))
      (node (ref "U2") (pin "37") (pinfunction "GND_37") (pintype "bidirectional"))
      (node (ref "U2") (pin "39") (pinfunction "GND_39") (pintype "bidirectional"))
      (node (ref "U3") (pin "GND") (pinfunction "GND_GND") (pintype "input"))
      (node (ref "X1") (pin "1") (pinfunction "1_1") (pintype "power_in"))
      (node (ref "X1") (pin "3") (pinfunction "3_3") (pintype "power_in"))
    )
    (net (code "55") (name "Net-(JP3-Pad1)") (class "Default")
      (node (ref "JP3") (pin "1") (pinfunction "1_1") (pintype "passive"))
      (node (ref "U3") (pin "OUT") (pinfunction "OUT_OUT") (pintype "output"))
    )
    (net (code "56") (name "VIN") (class "Default")
      (node (ref "C16") (pin "1") (pinfunction "+_1") (pintype "passive"))
      (node (ref "C17") (pin "1") (pinfunction "+_1") (pintype "passive"))
      (node (ref "C2") (pin "1") (pinfunction "+_1") (pintype "passive"))
      (node (ref "IC2") (pin "8") (pinfunction "VCC2_8") (pintype "power_in"))
      (node (ref "IC3") (pin "8") (pinfunction "VCC2_8") (pintype "power_in"))
      (node (ref "JP3") (pin "3") (pinfunction "3_3") (pintype "passive"))
      (node (ref "JP4") (pin "2") (pinfunction "2_2") (pintype "passive"))
      (node (ref "U3") (pin "IN") (pinfunction "IN_IN") (pintype "input"))
      (node (ref "X1") (pin "2") (pinfunction "2_2") (pintype "power_in"))
    )
    (net (code "57") (name "unconnected-(JP8-Pad2)") (class "Default")
      (node (ref "JP8") (pin "2") (pinfunction "2_2") (pintype "passive"))
    )
    (net (code "58") (name "unconnected-(JP8-Pad3)") (class "Default")
      (node (ref "JP8") (pin "3") (pinfunction "3_3") (pintype "passive"))
    )
    (net (code "59") (name "unconnected-(JP8-Pad6)") (class "Default")
      (node (ref "JP8") (pin "6") (pinfunction "6_6") (pintype "passive"))
    )
    (net (code "60") (name "unconnected-(U1-5V_OUT-Pad1)") (class "Default")
      (node (ref "U1") (pin "1") (pinfunction "5V_OUT_1") (pintype "bidirectional"))
    )
    (net (code "61") (name "unconnected-(U1-PIN24{slash}SCK-Pad30)") (class "Default")
      (node (ref "U1") (pin "30") (pinfunction "PIN24/SCK_30") (pintype "bidirectional"))
    )
    (net (code "62") (name "unconnected-(U1-PIN25{slash}SDI-Pad31)") (class "Default")
      (node (ref "U1") (pin "31") (pinfunction "PIN25/SDI_31") (pintype "bidirectional"))
    )
    (net (code "63") (name "unconnected-(U1-PIN26{slash}SDO-Pad32)") (class "Default")
      (node (ref "U1") (pin "32") (pinfunction "PIN26/SDO_32") (pintype "bidirectional"))
    )
    (net (code "64") (name "unconnected-(U1-PIN27{slash}SS-Pad33)") (class "Default")
      (node (ref "U1") (pin "33") (pinfunction "PIN27/SS_33") (pintype "bidirectional"))
    )
    (net (code "65") (name "unconnected-(U2-5V_OUT-Pad1)") (class "Default")
      (node (ref "U2") (pin "1") (pinfunction "5V_OUT_1") (pintype "bidirectional"))
    )
  )
)
